# c-mote.net
KiCad netlist of a schematic drawn in Altium Designer
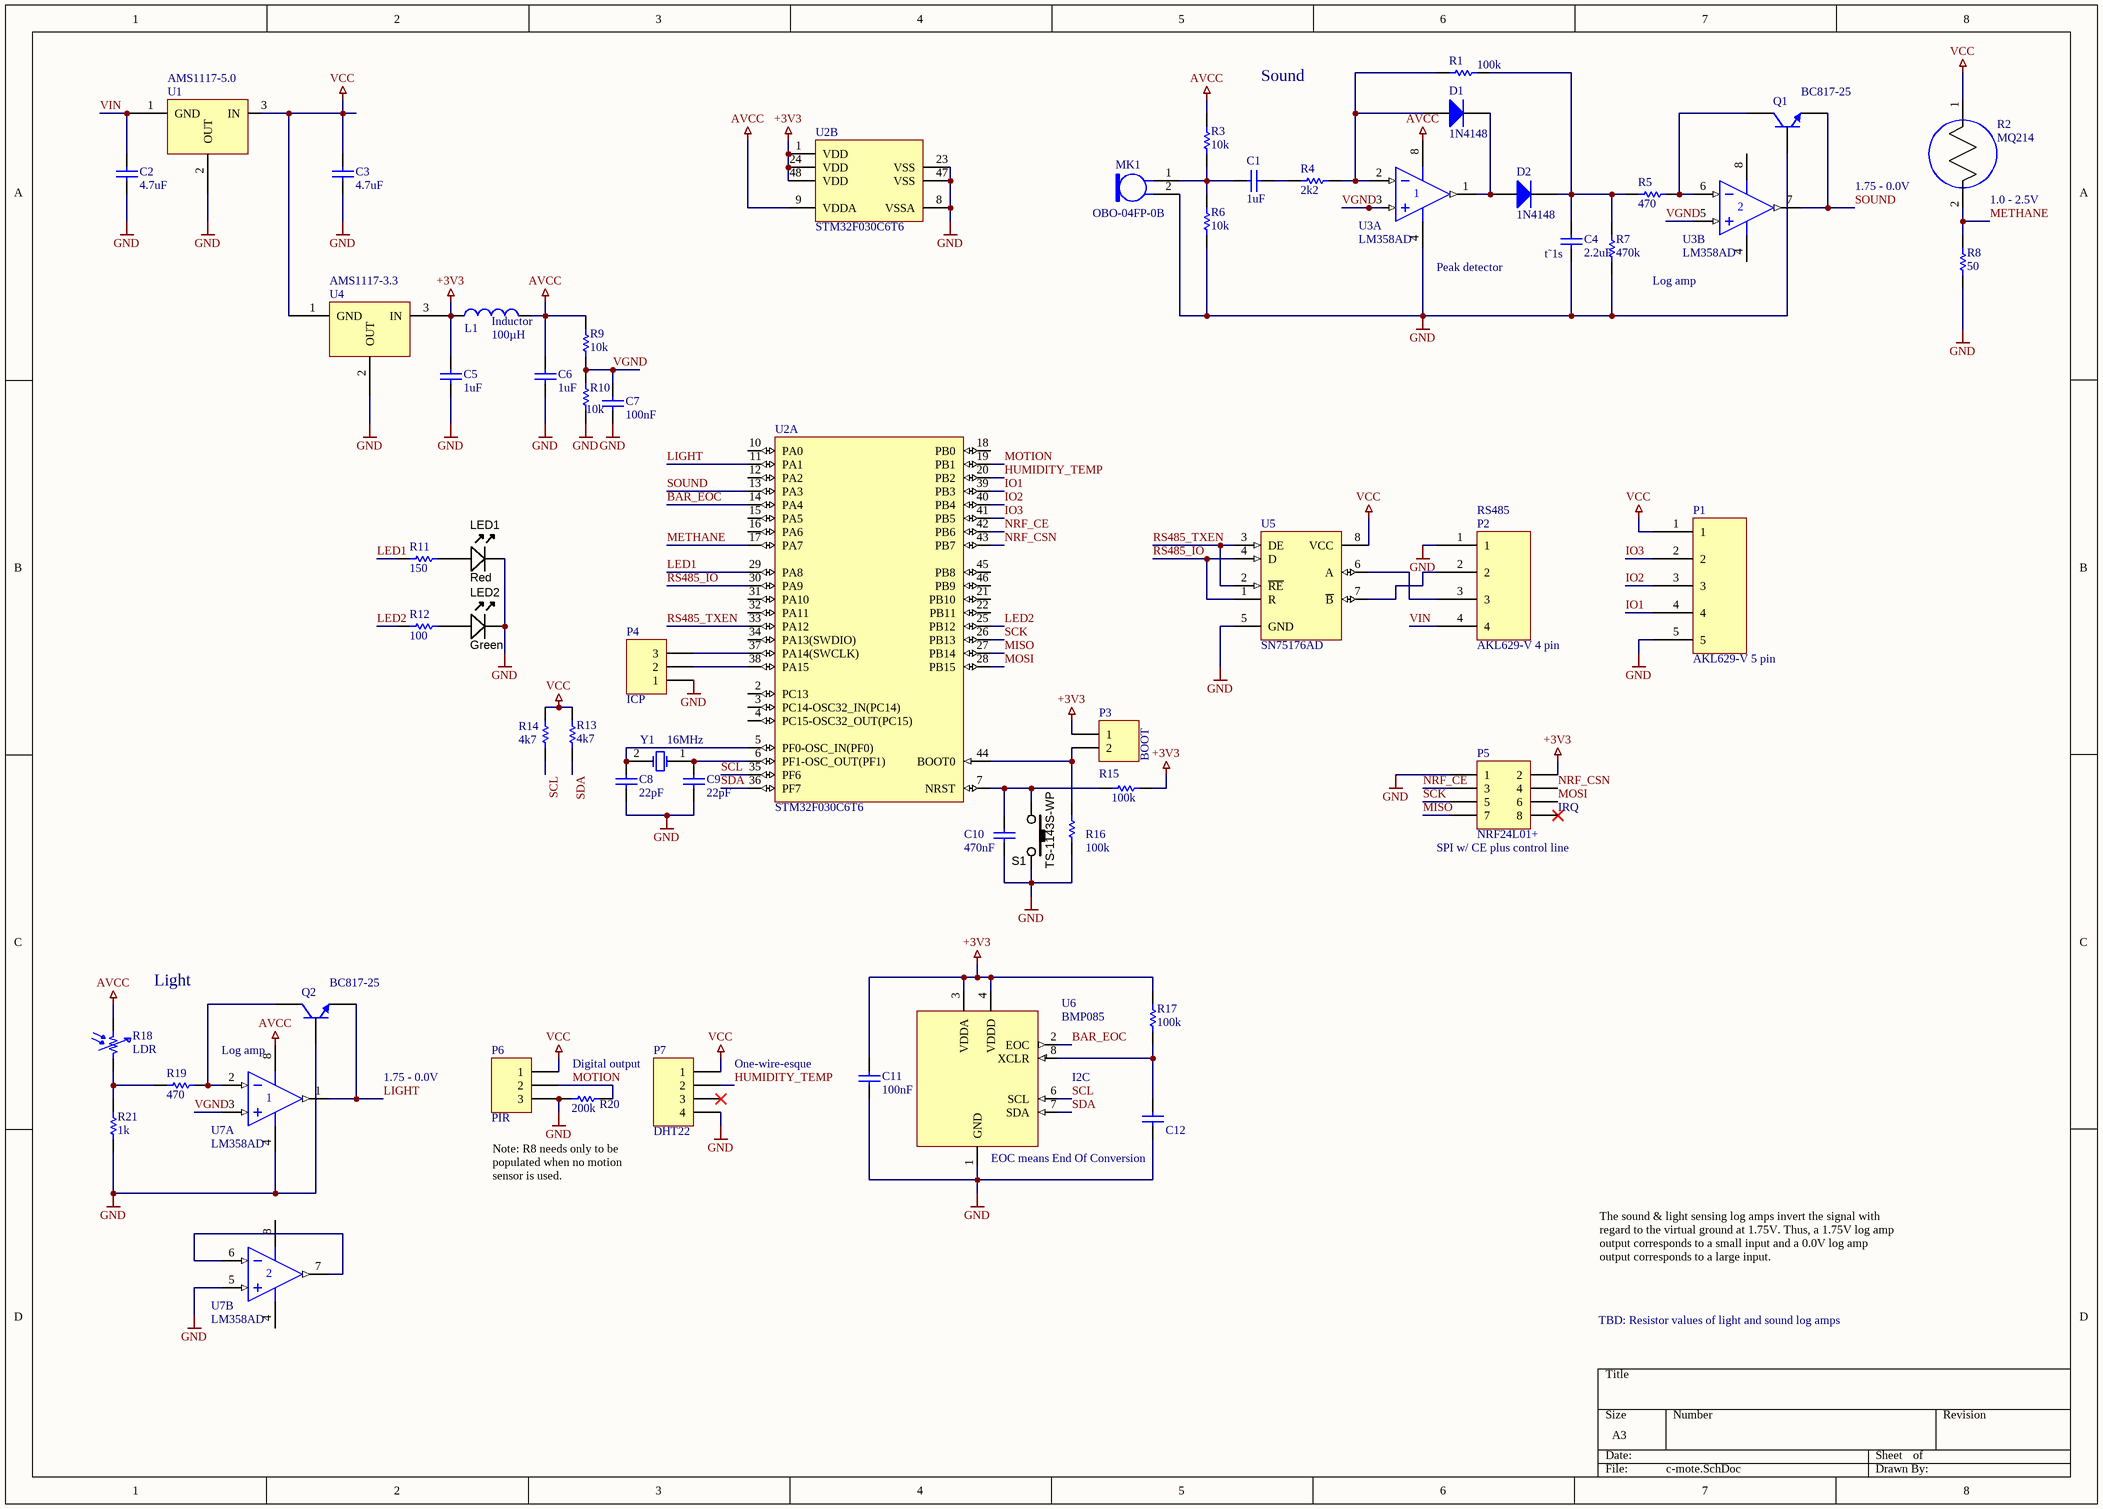
[diagram p0: c-mote.SchDoc]

(export (version "E")
  (design (tool "Eeschema 10.0.6"))
  (components
    (comp (ref "C1")
      (value "1uF")
      (footprint "CAPC0805(2012)145_M")
      (description "CAP 1uF 10V ±20% 0805 (2012 Metric) Thickness 1.45mm SMD")
      (fields (field (name "TOLERANCE") "±20%") (field (name "Comment") "CAP 1uF 10V 0805(2012)"))
      (libsource (lib "Altium Content Vault") (part "CMP-1036-04740-1"))
    )
    (comp (ref "C2")
      (value "4.7uF")
      (footprint "CAPC0805(2012)145_N")
      (description "CAP 4.7uF 10V ±20% 0805 (2012 Metric) Thickness 1.45mm SMD")
      (fields (field (name "TOLERANCE") "±20%") (field (name "Comment") "CAP 4.7uF 10V 0805(2012)"))
      (libsource (lib "Altium Content Vault") (part "CMP-1036-04884-1"))
    )
    (comp (ref "C3")
      (value "4.7uF")
      (footprint "CAPC0805(2012)145_N")
      (description "CAP 4.7uF 10V ±20% 0805 (2012 Metric) Thickness 1.45mm SMD")
      (fields (field (name "TOLERANCE") "±20%") (field (name "Comment") "CAP 4.7uF 10V 0805(2012)"))
      (libsource (lib "Altium Content Vault") (part "CMP-1036-04884-1"))
    )
    (comp (ref "C4")
      (value "2.2uF")
      (footprint "CAPC0805(2012)145_N")
      (description "CAP 2.2uF 10V ±10% 0805 (2012 Metric) Thickness 1.45mm SMD")
      (fields (field (name "TOLERANCE") "±10%") (field (name "Comment") "CAP 2.2uF 10V 0805(2012)"))
      (libsource (lib "Altium Content Vault") (part "CMP-1036-04824-1"))
    )
    (comp (ref "C5")
      (value "1uF")
      (footprint "CAPC0805(2012)145_M")
      (description "CAP 1uF 10V ±20% 0805 (2012 Metric) Thickness 1.45mm SMD")
      (fields (field (name "TOLERANCE") "±20%") (field (name "Comment") "CAP 1uF 10V 0805(2012)"))
      (libsource (lib "Altium Content Vault") (part "CMP-1036-04740-1"))
    )
    (comp (ref "C6")
      (value "1uF")
      (footprint "CAPC0805(2012)145_M")
      (description "CAP 1uF 10V ±20% 0805 (2012 Metric) Thickness 1.45mm SMD")
      (fields (field (name "TOLERANCE") "±20%") (field (name "Comment") "CAP 1uF 10V 0805(2012)"))
      (libsource (lib "Altium Content Vault") (part "CMP-1036-04740-1"))
    )
    (comp (ref "C7")
      (value "100nF")
      (footprint "CAPC0805(2012)100_M")
      (description "CAP 100nF 10V ±10% 0805 (2012 Metric) Thickness 1mm SMD")
      (fields (field (name "TOLERANCE") "±10%") (field (name "Comment") "CAP 100nF 10V 0805(2012)"))
      (libsource (lib "Altium Content Vault") (part "CMP-1036-04394-1"))
    )
    (comp (ref "C8")
      (value "22pF")
      (footprint "CAPC0805(2012)100_M")
      (description "CAP 22pF 10V ±5% 0805 (2012 Metric) Thickness 1mm SMD")
      (fields (field (name "TOLERANCE") "±5%") (field (name "Comment") "CAP 22pF 10V 0805(2012)"))
      (libsource (lib "Altium Content Vault") (part "CMP-1036-01210-1"))
    )
    (comp (ref "C9")
      (value "22pF")
      (footprint "CAPC0805(2012)100_M")
      (description "CAP 22pF 10V ±5% 0805 (2012 Metric) Thickness 1mm SMD")
      (fields (field (name "TOLERANCE") "±5%") (field (name "Comment") "CAP 22pF 10V 0805(2012)"))
      (libsource (lib "Altium Content Vault") (part "CMP-1036-01210-1"))
    )
    (comp (ref "C10")
      (value "470nF")
      (footprint "CAPC0805(2012)145_M")
      (description "CAP 470nF 10V ±10% 0805 (2012 Metric) Thickness 1.45mm SMD")
      (fields (field (name "TOLERANCE") "±10%") (field (name "Comment") "CAP 470nF 10V 0805(2012)"))
      (libsource (lib "Altium Content Vault") (part "CMP-1036-04631-1"))
    )
    (comp (ref "C11")
      (value "100nF")
      (footprint "CAPC0805(2012)100_M")
      (description "CAP 100nF 10V ±10% 0805 (2012 Metric) Thickness 1mm SMD")
      (fields (field (name "TOLERANCE") "±10%") (field (name "Comment") "CAP 100nF 10V 0805(2012)"))
      (libsource (lib "Altium Content Vault") (part "CMP-1036-04394-1"))
    )
    (comp (ref "C12")
      (value "CAP 10nF 10V 0805(2012)")
      (footprint "CAPC0805(2012)100_L")
      (description "CAP 10nF 10V ±10% 0805 (2012 Metric) Thickness 1mm SMD")
      (fields (field (name "TOLERANCE") "±10%"))
      (libsource (lib "Altium Content Vault") (part "CAP"))
    )
    (comp (ref "D1")
      (value "1N4148")
      (footprint "SOD-323F")
      (description "High Conductance Fast Diode")
      (fields (field (name "PUBLISHER") "Altium Limited"))
      (libsource (lib "FSC Discrete Diode") (part "1N4148"))
    )
    (comp (ref "D2")
      (value "1N4148")
      (footprint "SOD-323F")
      (description "High Conductance Fast Diode")
      (fields (field (name "PUBLISHER") "Altium Limited"))
      (libsource (lib "FSC Discrete Diode") (part "1N4148"))
    )
    (comp (ref "L1")
      (value "Inductor")
      (footprint "INDC3216")
      (fields (field (name "ALTIUM_VALUE") "100µH") (field (name "PUBLISHER") "Altium Limited"))
      (libsource (lib "Miscellaneous Devices") (part "Inductor"))
    )
    (comp (ref "LED1")
      (value "~")
      (footprint "LED-0805-K")
      (description "LED 0805 SMD Red 6mcd 621nm")
      (fields (field (name "COLOR") "Red"))
      (libsource (lib "PBL - Light Sources") (part "LED_SMD_Red_0805_6mcd"))
    )
    (comp (ref "LED2")
      (value "~")
      (footprint "LED-0805-K")
      (description "LED, 0805 SMD, Green")
      (fields (field (name "COLOR") "Green"))
      (libsource (lib "PBL - Light Sources") (part "LED_SMD_Green_0805_6mcd"))
    )
    (comp (ref "MK1")
      (value "OBO-04FP-0B")
      (footprint "OBO-04FP-0B")
      (description "Microphone")
      (fields (field (name "PUBLISHER") "Altium Limited"))
      (libsource (lib "Miscellaneous Devices") (part "Mic2"))
    )
    (comp (ref "P1") (value "AKL629-V 5 pin") (libsource (lib "auxcomp") (part "AKL629-V 5 pin")))
    (comp (ref "P2") (value "AKL629-V 4 pin") (libsource (lib "auxcomp") (part "AKL629-V 4 pin")))
    (comp (ref "P3")
      (value "BOOT")
      (footprint "HDR1X2")
      (description "Header, 2-Pin")
      (fields (field (name "PUBLISHER") "Altium Limited"))
      (libsource (lib "Miscellaneous Connectors") (part "Header 2"))
    )
    (comp (ref "P4")
      (value "ICP")
      (footprint "HDR1X3")
      (description "Header, 3-Pin")
      (fields (field (name "PUBLISHER") "Altium Limited"))
      (libsource (lib "") (part "Header 3_1"))
    )
    (comp (ref "P5")
      (value "NRF24L01+")
      (footprint "HDR2X4")
      (description "Header, 4-Pin, Dual row")
      (fields (field (name "PUBLISHER") "Altium Limited"))
      (libsource (lib "Miscellaneous Connectors") (part "Header 4X2"))
    )
    (comp (ref "P6")
      (value "PIR")
      (footprint "China-PIR sensor")
      (description "Header, 3-Pin")
      (fields (field (name "PUBLISHER") "Altium Limited"))
      (libsource (lib "Miscellaneous Connectors") (part "Header 3"))
    )
    (comp (ref "P7")
      (value "DHT22")
      (footprint "DHT22-H")
      (description "Header, 4-Pin")
      (fields (field (name "PUBLISHER") "Altium Limited"))
      (libsource (lib "Miscellaneous Connectors") (part "Header 4"))
    )
    (comp (ref "Q1")
      (value "BC817-25")
      (footprint "SOT23_N")
      (description "NPN General Purpose Amplifier")
      (fields (field (name "PUBLISHER") "Altium Limited"))
      (libsource (lib "FSC Discrete BJT") (part "BC817-25"))
    )
    (comp (ref "Q2")
      (value "BC817-25")
      (footprint "SOT23_N")
      (description "NPN General Purpose Amplifier")
      (fields (field (name "PUBLISHER") "Altium Limited"))
      (libsource (lib "FSC Discrete BJT") (part "BC817-25"))
    )
    (comp (ref "R1")
      (value "100k")
      (footprint "6-0805")
      (fields (field (name "PUBLISHER") "Altium Limited"))
      (libsource (lib "Panasonic Resistor") (part "ERJ6RB"))
    )
    (comp (ref "R2") (value "MQ214") (footprint "MQ214") (libsource (lib "auxcomp") (part "MQ214")))
    (comp (ref "R3")
      (value "10k")
      (footprint "6-0805")
      (fields (field (name "PUBLISHER") "Altium Limited"))
      (libsource (lib "Panasonic Resistor") (part "ERJ6RB"))
    )
    (comp (ref "R4")
      (value "2k2")
      (footprint "6-0805")
      (fields (field (name "PUBLISHER") "Altium Limited"))
      (libsource (lib "Panasonic Resistor") (part "ERJ6RB"))
    )
    (comp (ref "R5")
      (value "470")
      (footprint "6-0805")
      (fields (field (name "PUBLISHER") "Altium Limited"))
      (libsource (lib "Panasonic Resistor") (part "ERJ6RB"))
    )
    (comp (ref "R6")
      (value "10k")
      (footprint "6-0805")
      (fields (field (name "PUBLISHER") "Altium Limited"))
      (libsource (lib "Panasonic Resistor") (part "ERJ6RB"))
    )
    (comp (ref "R7")
      (value "470k")
      (footprint "6-0805")
      (fields (field (name "PUBLISHER") "Altium Limited"))
      (libsource (lib "Panasonic Resistor") (part "ERJ6RB"))
    )
    (comp (ref "R8")
      (value "50")
      (footprint "6-0805")
      (fields (field (name "PUBLISHER") "Altium Limited"))
      (libsource (lib "Panasonic Resistor") (part "ERJ6RB"))
    )
    (comp (ref "R9")
      (value "10k")
      (footprint "6-0805")
      (fields (field (name "PUBLISHER") "Altium Limited"))
      (libsource (lib "Panasonic Resistor") (part "ERJ6RB"))
    )
    (comp (ref "R10")
      (value "10k")
      (footprint "6-0805")
      (fields (field (name "PUBLISHER") "Altium Limited"))
      (libsource (lib "Panasonic Resistor") (part "ERJ6RB"))
    )
    (comp (ref "R11")
      (value "150")
      (footprint "6-0805")
      (fields (field (name "PUBLISHER") "Altium Limited"))
      (libsource (lib "Panasonic Resistor") (part "ERJ6RB"))
    )
    (comp (ref "R12")
      (value "100")
      (footprint "6-0805")
      (fields (field (name "PUBLISHER") "Altium Limited"))
      (libsource (lib "Panasonic Resistor") (part "ERJ6RB"))
    )
    (comp (ref "R13")
      (value "4k7")
      (footprint "6-0805")
      (fields (field (name "PUBLISHER") "Altium Limited"))
      (libsource (lib "Panasonic Resistor") (part "ERJ6RB"))
    )
    (comp (ref "R14")
      (value "4k7")
      (footprint "6-0805")
      (fields (field (name "PUBLISHER") "Altium Limited"))
      (libsource (lib "Panasonic Resistor") (part "ERJ6RB"))
    )
    (comp (ref "R15")
      (value "100k")
      (footprint "6-0805")
      (fields (field (name "PUBLISHER") "Altium Limited"))
      (libsource (lib "Panasonic Resistor") (part "ERJ6RB"))
    )
    (comp (ref "R16")
      (value "100k")
      (footprint "6-0805")
      (fields (field (name "PUBLISHER") "Altium Limited"))
      (libsource (lib "Panasonic Resistor") (part "ERJ6RB"))
    )
    (comp (ref "R17")
      (value "100k")
      (footprint "6-0805")
      (fields (field (name "PUBLISHER") "Altium Limited"))
      (libsource (lib "Panasonic Resistor") (part "ERJ6RB"))
    )
    (comp (ref "R18")
      (value "LDR")
      (footprint "KE-10720")
      (description "KE-10720")
      (libsource (lib "auxcomp") (part "LDR"))
    )
    (comp (ref "R19")
      (value "470")
      (footprint "6-0805")
      (fields (field (name "PUBLISHER") "Altium Limited"))
      (libsource (lib "Panasonic Resistor") (part "ERJ6RB"))
    )
    (comp (ref "R20")
      (value "200k")
      (footprint "6-0805")
      (fields (field (name "PUBLISHER") "Altium Limited"))
      (libsource (lib "Panasonic Resistor") (part "ERJ6RB"))
    )
    (comp (ref "R21")
      (value "1k")
      (footprint "6-0805")
      (fields (field (name "PUBLISHER") "Altium Limited"))
      (libsource (lib "Panasonic Resistor") (part "ERJ6RB"))
    )
    (comp (ref "S1")
      (value "TS-1143S-WP")
      (footprint "TS-1143S")
      (description "Switch SMD Tact 4.3mm Stem")
      (libsource (lib "PBL - Switches") (part "SW_SMD_PB_4.3mm"))
    )
    (comp (ref "U1") (value "AMS1117-5.0") (footprint "SOT223") (libsource (lib "auxcomp") (part "AMS1117")))
    (comp (ref "U2")
      (value "STM32F030C6T6")
      (footprint "STM-LQFP48_N")
      (libsource (lib "Altium Content Vault") (part "MC-ARM-STM32F030-SQ48"))
    )
    (comp (ref "U3")
      (value "LM358AD")
      (footprint "SOIC127P600X175-8AN")
      (description "Dual Operational Amplifier")
      (fields (field (name "PUBLISHER") "Altium Limited"))
      (libsource (lib "TI Operational Amplifier") (part "LM358AD"))
    )
    (comp (ref "U4") (value "AMS1117-3.3") (footprint "SOT223") (libsource (lib "auxcomp") (part "AMS1117")))
    (comp (ref "U5")
      (value "SN75176AD")
      (footprint "SOIC127P600X175-8AN")
      (description "Differential Bus Transceiver")
      (fields (field (name "PUBLISHER") "Altium Limited"))
      (libsource (lib "TI Interface Line Transceiver") (part "SN75176AD"))
    )
    (comp (ref "U6") (value "BMP085") (footprint "BMP085") (libsource (lib "auxcomp") (part "BMP085")))
    (comp (ref "U7")
      (value "LM358AD")
      (footprint "SOIC127P600X175-8AN")
      (description "Dual Operational Amplifier")
      (fields (field (name "PUBLISHER") "Altium Limited"))
      (libsource (lib "TI Operational Amplifier") (part "LM358AD"))
    )
    (comp (ref "Y1")
      (value "16MHz")
      (footprint "HC49/US")
      (description "Crystal")
      (fields (field (name "PUBLISHER") "Altium Limited"))
      (libsource (lib "Miscellaneous Devices") (part "XTAL"))
    )
  )
  (nets
    (net (code "1") (name "+3V3") (class "Default")
      (node (ref "C11") (pin "2") (pinfunction "2_2") (pintype "passive"))
      (node (ref "C5") (pin "2") (pinfunction "2_2") (pintype "passive"))
      (node (ref "L1") (pin "1") (pinfunction "1_1") (pintype "passive"))
      (node (ref "P3") (pin "1") (pinfunction "1_1") (pintype "passive"))
      (node (ref "P5") (pin "2") (pinfunction "2_2") (pintype "passive"))
      (node (ref "R15") (pin "2") (pinfunction "2_2") (pintype "passive"))
      (node (ref "R17") (pin "2") (pinfunction "2_2") (pintype "passive"))
      (node (ref "U2") (pin "1") (pinfunction "VDD_1") (pintype "power_in"))
      (node (ref "U2") (pin "24") (pinfunction "VDD_24") (pintype "power_in"))
      (node (ref "U2") (pin "48") (pinfunction "VDD_48") (pintype "power_in"))
      (node (ref "U4") (pin "3") (pinfunction "IN_3") (pintype "passive"))
      (node (ref "U6") (pin "3") (pinfunction "VDDA_3") (pintype "power_in"))
      (node (ref "U6") (pin "4") (pinfunction "VDDD_4") (pintype "power_in"))
    )
    (net (code "2") (name "/BAR_EOC") (class "Default")
      (node (ref "U2") (pin "14") (pinfunction "PA4_14") (pintype "bidirectional"))
      (node (ref "U6") (pin "2") (pinfunction "EOC_2") (pintype "output"))
    )
    (net (code "3") (name "/HUMIDITY_TEMP") (class "Default")
      (node (ref "P7") (pin "2") (pinfunction "2_2") (pintype "passive"))
      (node (ref "U2") (pin "20") (pinfunction "PB2_20") (pintype "bidirectional"))
    )
    (net (code "4") (name "/IO1") (class "Default")
      (node (ref "P1") (pin "4") (pinfunction "4_4") (pintype "passive"))
      (node (ref "U2") (pin "39") (pinfunction "PB3_39") (pintype "bidirectional"))
    )
    (net (code "5") (name "/IO2") (class "Default")
      (node (ref "P1") (pin "3") (pinfunction "3_3") (pintype "passive"))
      (node (ref "U2") (pin "40") (pinfunction "PB4_40") (pintype "bidirectional"))
    )
    (net (code "6") (name "/IO3") (class "Default")
      (node (ref "P1") (pin "2") (pinfunction "2_2") (pintype "passive"))
      (node (ref "U2") (pin "41") (pinfunction "PB5_41") (pintype "bidirectional"))
    )
    (net (code "7") (name "/LED1") (class "Default")
      (node (ref "R11") (pin "2") (pinfunction "2_2") (pintype "passive"))
      (node (ref "U2") (pin "29") (pinfunction "PA8_29") (pintype "bidirectional"))
    )
    (net (code "8") (name "/LED2") (class "Default")
      (node (ref "R12") (pin "2") (pinfunction "2_2") (pintype "passive"))
      (node (ref "U2") (pin "25") (pinfunction "PB12_25") (pintype "bidirectional"))
    )
    (net (code "9") (name "/LIGHT") (class "Default")
      (node (ref "Q2") (pin "2") (pinfunction "E_2") (pintype "passive"))
      (node (ref "U2") (pin "11") (pinfunction "PA1_11") (pintype "bidirectional"))
      (node (ref "U7") (pin "1") (pinfunction "OUT_1") (pintype "output"))
    )
    (net (code "10") (name "/METHANE") (class "Default")
      (node (ref "R2") (pin "2") (pintype "passive"))
      (node (ref "R8") (pin "2") (pinfunction "2_2") (pintype "passive"))
      (node (ref "U2") (pin "17") (pinfunction "PA7_17") (pintype "bidirectional"))
    )
    (net (code "11") (name "/MISO") (class "Default")
      (node (ref "P5") (pin "7") (pinfunction "7_7") (pintype "passive"))
      (node (ref "U2") (pin "27") (pinfunction "PB14_27") (pintype "bidirectional"))
    )
    (net (code "12") (name "/MOSI") (class "Default")
      (node (ref "P5") (pin "6") (pinfunction "6_6") (pintype "passive"))
      (node (ref "U2") (pin "28") (pinfunction "PB15_28") (pintype "bidirectional"))
    )
    (net (code "13") (name "/MOTION") (class "Default")
      (node (ref "P6") (pin "2") (pinfunction "2_2") (pintype "passive"))
      (node (ref "R20") (pin "2") (pinfunction "2_2") (pintype "passive"))
      (node (ref "U2") (pin "19") (pinfunction "PB1_19") (pintype "bidirectional"))
    )
    (net (code "14") (name "/NRF_CE") (class "Default")
      (node (ref "P5") (pin "3") (pinfunction "3_3") (pintype "passive"))
      (node (ref "U2") (pin "42") (pinfunction "PB6_42") (pintype "bidirectional"))
    )
    (net (code "15") (name "/NRF_CSN") (class "Default")
      (node (ref "P5") (pin "4") (pinfunction "4_4") (pintype "passive"))
      (node (ref "U2") (pin "43") (pinfunction "PB7_43") (pintype "bidirectional"))
    )
    (net (code "16") (name "/RS485_IO") (class "Default")
      (node (ref "U2") (pin "30") (pinfunction "PA9_30") (pintype "bidirectional"))
      (node (ref "U5") (pin "1") (pinfunction "R_1") (pintype "tri_state"))
      (node (ref "U5") (pin "4") (pinfunction "D_4") (pintype "input"))
    )
    (net (code "17") (name "/RS485_TXEN") (class "Default")
      (node (ref "U2") (pin "33") (pinfunction "PA12_33") (pintype "bidirectional"))
      (node (ref "U5") (pin "2") (pinfunction "~{RE}_2") (pintype "input"))
      (node (ref "U5") (pin "3") (pinfunction "DE_3") (pintype "input"))
    )
    (net (code "18") (name "/SCK") (class "Default")
      (node (ref "P5") (pin "5") (pinfunction "5_5") (pintype "passive"))
      (node (ref "U2") (pin "26") (pinfunction "PB13_26") (pintype "bidirectional"))
    )
    (net (code "19") (name "/SCL") (class "Default")
      (node (ref "R14") (pin "2") (pinfunction "2_2") (pintype "passive"))
      (node (ref "U2") (pin "35") (pinfunction "PF6_35") (pintype "bidirectional"))
      (node (ref "U6") (pin "6") (pinfunction "SCL_6") (pintype "input"))
    )
    (net (code "20") (name "/SDA") (class "Default")
      (node (ref "R13") (pin "2") (pinfunction "2_2") (pintype "passive"))
      (node (ref "U2") (pin "36") (pinfunction "PF7_36") (pintype "bidirectional"))
      (node (ref "U6") (pin "7") (pinfunction "SDA_7") (pintype "input"))
    )
    (net (code "21") (name "/SOUND") (class "Default")
      (node (ref "Q1") (pin "2") (pinfunction "E_2") (pintype "passive"))
      (node (ref "U2") (pin "13") (pinfunction "PA3_13") (pintype "bidirectional"))
      (node (ref "U3") (pin "7") (pinfunction "OUT_7") (pintype "output"))
    )
    (net (code "22") (name "/VGND") (class "Default")
      (node (ref "C7") (pin "2") (pinfunction "2_2") (pintype "passive"))
      (node (ref "R10") (pin "2") (pinfunction "2_2") (pintype "passive"))
      (node (ref "R9") (pin "1") (pinfunction "1_1") (pintype "passive"))
      (node (ref "U3") (pin "3") (pinfunction "IN+_3") (pintype "input"))
      (node (ref "U3") (pin "5") (pinfunction "IN+_5") (pintype "input"))
      (node (ref "U7") (pin "3") (pinfunction "IN+_3") (pintype "input"))
    )
    (net (code "23") (name "/VIN") (class "Default")
      (node (ref "C2") (pin "2") (pinfunction "2_2") (pintype "passive"))
      (node (ref "P2") (pin "4") (pinfunction "4_4") (pintype "passive"))
      (node (ref "U1") (pin "1") (pinfunction "GND_1") (pintype "passive"))
    )
    (net (code "24") (name "AVCC") (class "Default")
      (node (ref "C6") (pin "2") (pinfunction "2_2") (pintype "passive"))
      (node (ref "L1") (pin "2") (pinfunction "2_2") (pintype "passive"))
      (node (ref "R18") (pin "1") (pinfunction "1_1") (pintype "passive"))
      (node (ref "R3") (pin "2") (pinfunction "2_2") (pintype "passive"))
      (node (ref "R9") (pin "2") (pinfunction "2_2") (pintype "passive"))
      (node (ref "U2") (pin "9") (pinfunction "VDDA_9") (pintype "power_in"))
      (node (ref "U3") (pin "8") (pinfunction "V+_8") (pintype "power_in"))
      (node (ref "U7") (pin "8") (pinfunction "V+_8") (pintype "power_in"))
    )
    (net (code "25") (name "GND") (class "Default")
      (node (ref "C10") (pin "1") (pinfunction "1_1") (pintype "passive"))
      (node (ref "C11") (pin "1") (pinfunction "1_1") (pintype "passive"))
      (node (ref "C12") (pin "1") (pinfunction "1_1") (pintype "passive"))
      (node (ref "C2") (pin "1") (pinfunction "1_1") (pintype "passive"))
      (node (ref "C3") (pin "1") (pinfunction "1_1") (pintype "passive"))
      (node (ref "C4") (pin "1") (pinfunction "1_1") (pintype "passive"))
      (node (ref "C5") (pin "1") (pinfunction "1_1") (pintype "passive"))
      (node (ref "C6") (pin "1") (pinfunction "1_1") (pintype "passive"))
      (node (ref "C7") (pin "1") (pinfunction "1_1") (pintype "passive"))
      (node (ref "C8") (pin "1") (pinfunction "1_1") (pintype "passive"))
      (node (ref "C9") (pin "1") (pinfunction "1_1") (pintype "passive"))
      (node (ref "LED1") (pin "K") (pinfunction "K_K") (pintype "passive"))
      (node (ref "LED2") (pin "K") (pinfunction "K_K") (pintype "passive"))
      (node (ref "MK1") (pin "2") (pinfunction "2_2") (pintype "passive"))
      (node (ref "P1") (pin "5") (pinfunction "5_5") (pintype "passive"))
      (node (ref "P2") (pin "1") (pinfunction "1_1") (pintype "passive"))
      (node (ref "P4") (pin "1") (pinfunction "1_1") (pintype "passive"))
      (node (ref "P5") (pin "1") (pinfunction "1_1") (pintype "passive"))
      (node (ref "P6") (pin "3") (pinfunction "3_3") (pintype "passive"))
      (node (ref "P7") (pin "4") (pinfunction "4_4") (pintype "passive"))
      (node (ref "Q1") (pin "1") (pinfunction "B_1") (pintype "passive"))
      (node (ref "Q2") (pin "1") (pinfunction "B_1") (pintype "passive"))
      (node (ref "R10") (pin "1") (pinfunction "1_1") (pintype "passive"))
      (node (ref "R16") (pin "1") (pinfunction "1_1") (pintype "passive"))
      (node (ref "R20") (pin "1") (pinfunction "1_1") (pintype "passive"))
      (node (ref "R21") (pin "2") (pinfunction "2_2") (pintype "passive"))
      (node (ref "R6") (pin "1") (pinfunction "1_1") (pintype "passive"))
      (node (ref "R7") (pin "2") (pinfunction "2_2") (pintype "passive"))
      (node (ref "R8") (pin "1") (pinfunction "1_1") (pintype "passive"))
      (node (ref "S1") (pin "2") (pintype "passive"))
      (node (ref "U1") (pin "2") (pinfunction "OUT_2") (pintype "passive"))
      (node (ref "U2") (pin "23") (pinfunction "VSS_23") (pintype "power_in"))
      (node (ref "U2") (pin "47") (pinfunction "VSS_47") (pintype "power_in"))
      (node (ref "U2") (pin "8") (pinfunction "VSSA_8") (pintype "power_in"))
      (node (ref "U3") (pin "4") (pinfunction "V-_4") (pintype "power_in"))
      (node (ref "U4") (pin "2") (pinfunction "OUT_2") (pintype "passive"))
      (node (ref "U5") (pin "5") (pinfunction "GND_5") (pintype "power_in"))
      (node (ref "U6") (pin "1") (pinfunction "GND_1") (pintype "power_in"))
      (node (ref "U7") (pin "4") (pinfunction "V-_4") (pintype "power_in"))
      (node (ref "U7") (pin "5") (pinfunction "IN+_5") (pintype "input"))
    )
    (net (code "26") (name "Net-(C1-Pad1)") (class "Default")
      (node (ref "C1") (pin "1") (pinfunction "1_1") (pintype "passive"))
      (node (ref "R4") (pin "2") (pinfunction "2_2") (pintype "passive"))
    )
    (net (code "27") (name "Net-(C1-Pad2)") (class "Default")
      (node (ref "C1") (pin "2") (pinfunction "2_2") (pintype "passive"))
      (node (ref "MK1") (pin "1") (pinfunction "1_1") (pintype "passive"))
      (node (ref "R3") (pin "1") (pinfunction "1_1") (pintype "passive"))
      (node (ref "R6") (pin "2") (pinfunction "2_2") (pintype "passive"))
    )
    (net (code "28") (name "Net-(D1-A)") (class "Default")
      (node (ref "D1") (pin "1") (pinfunction "A_1") (pintype "passive"))
      (node (ref "R1") (pin "2") (pinfunction "2_2") (pintype "passive"))
      (node (ref "R4") (pin "1") (pinfunction "1_1") (pintype "passive"))
      (node (ref "U3") (pin "2") (pinfunction "IN-_2") (pintype "input"))
    )
    (net (code "29") (name "Net-(D1-K)") (class "Default")
      (node (ref "D1") (pin "2") (pinfunction "K_2") (pintype "passive"))
      (node (ref "D2") (pin "1") (pinfunction "A_1") (pintype "passive"))
      (node (ref "U3") (pin "1") (pinfunction "OUT_1") (pintype "output"))
    )
    (net (code "30") (name "Net-(D2-K)") (class "Default")
      (node (ref "C4") (pin "2") (pinfunction "2_2") (pintype "passive"))
      (node (ref "D2") (pin "2") (pinfunction "K_2") (pintype "passive"))
      (node (ref "R1") (pin "1") (pinfunction "1_1") (pintype "passive"))
      (node (ref "R5") (pin "1") (pinfunction "1_1") (pintype "passive"))
      (node (ref "R7") (pin "1") (pinfunction "1_1") (pintype "passive"))
    )
    (net (code "31") (name "Net-(LED1-PadA)") (class "Default")
      (node (ref "LED1") (pin "A") (pinfunction "A_A") (pintype "passive"))
      (node (ref "R11") (pin "1") (pinfunction "1_1") (pintype "passive"))
    )
    (net (code "32") (name "Net-(LED2-PadA)") (class "Default")
      (node (ref "LED2") (pin "A") (pinfunction "A_A") (pintype "passive"))
      (node (ref "R12") (pin "1") (pinfunction "1_1") (pintype "passive"))
    )
    (net (code "33") (name "Net-(Q1-C)") (class "Default")
      (node (ref "Q1") (pin "3") (pinfunction "C_3") (pintype "passive"))
      (node (ref "R5") (pin "2") (pinfunction "2_2") (pintype "passive"))
      (node (ref "U3") (pin "6") (pinfunction "IN-_6") (pintype "input"))
    )
    (net (code "34") (name "Net-(Q2-C)") (class "Default")
      (node (ref "Q2") (pin "3") (pinfunction "C_3") (pintype "passive"))
      (node (ref "R19") (pin "2") (pinfunction "2_2") (pintype "passive"))
      (node (ref "U7") (pin "2") (pinfunction "IN-_2") (pintype "input"))
    )
    (net (code "35") (name "Net-(R18-Pad2)") (class "Default")
      (node (ref "R18") (pin "2") (pinfunction "2_2") (pintype "passive"))
      (node (ref "R19") (pin "1") (pinfunction "1_1") (pintype "passive"))
      (node (ref "R21") (pin "1") (pinfunction "1_1") (pintype "passive"))
    )
    (net (code "36") (name "Net-(U2A-BOOT0)") (class "Default")
      (node (ref "P3") (pin "2") (pinfunction "2_2") (pintype "passive"))
      (node (ref "R16") (pin "2") (pinfunction "2_2") (pintype "passive"))
      (node (ref "U2") (pin "44") (pinfunction "BOOT0_44") (pintype "input"))
    )
    (net (code "37") (name "Net-(U2A-NRST)") (class "Default")
      (node (ref "C10") (pin "2") (pinfunction "2_2") (pintype "passive"))
      (node (ref "R15") (pin "1") (pinfunction "1_1") (pintype "passive"))
      (node (ref "S1") (pin "1") (pintype "passive"))
      (node (ref "U2") (pin "7") (pinfunction "NRST_7") (pintype "bidirectional"))
    )
    (net (code "38") (name "Net-(U2A-PA14(SWCLK))") (class "Default")
      (node (ref "P4") (pin "3") (pinfunction "3_3") (pintype "passive"))
      (node (ref "U2") (pin "37") (pinfunction "PA14(SWCLK)_37") (pintype "bidirectional"))
    )
    (net (code "39") (name "Net-(U2A-PA15)") (class "Default")
      (node (ref "P4") (pin "2") (pinfunction "2_2") (pintype "passive"))
      (node (ref "U2") (pin "38") (pinfunction "PA15_38") (pintype "bidirectional"))
    )
    (net (code "40") (name "Net-(U2A-PF0-OSC_IN(PF0))") (class "Default")
      (node (ref "C8") (pin "2") (pinfunction "2_2") (pintype "passive"))
      (node (ref "U2") (pin "5") (pinfunction "PF0-OSC_IN(PF0)_5") (pintype "bidirectional"))
      (node (ref "Y1") (pin "2") (pinfunction "OSC2_2") (pintype "passive"))
    )
    (net (code "41") (name "Net-(U2A-PF1-OSC_OUT(PF1))") (class "Default")
      (node (ref "C9") (pin "2") (pinfunction "2_2") (pintype "passive"))
      (node (ref "U2") (pin "6") (pinfunction "PF1-OSC_OUT(PF1)_6") (pintype "bidirectional"))
      (node (ref "Y1") (pin "1") (pinfunction "OSC1_1") (pintype "passive"))
    )
    (net (code "42") (name "Net-(U5-A)") (class "Default")
      (node (ref "P2") (pin "3") (pinfunction "3_3") (pintype "passive"))
      (node (ref "U5") (pin "6") (pinfunction "A_6") (pintype "bidirectional"))
    )
    (net (code "43") (name "Net-(U5-~{B})") (class "Default")
      (node (ref "P2") (pin "2") (pinfunction "2_2") (pintype "passive"))
      (node (ref "U5") (pin "7") (pinfunction "~{B}_7") (pintype "bidirectional"))
    )
    (net (code "44") (name "Net-(U6-XCLR)") (class "Default")
      (node (ref "C12") (pin "2") (pinfunction "2_2") (pintype "passive"))
      (node (ref "R17") (pin "1") (pinfunction "1_1") (pintype "passive"))
      (node (ref "U6") (pin "8") (pinfunction "XCLR_8") (pintype "input"))
    )
    (net (code "45") (name "Net-(U7B-IN-)") (class "Default")
      (node (ref "U7") (pin "6") (pinfunction "IN-_6") (pintype "input"))
      (node (ref "U7") (pin "7") (pinfunction "OUT_7") (pintype "output"))
    )
    (net (code "46") (name "VCC") (class "Default")
      (node (ref "C3") (pin "2") (pinfunction "2_2") (pintype "passive"))
      (node (ref "P1") (pin "1") (pinfunction "1_1") (pintype "passive"))
      (node (ref "P6") (pin "1") (pinfunction "1_1") (pintype "passive"))
      (node (ref "P7") (pin "1") (pinfunction "1_1") (pintype "passive"))
      (node (ref "R13") (pin "1") (pinfunction "1_1") (pintype "passive"))
      (node (ref "R14") (pin "1") (pinfunction "1_1") (pintype "passive"))
      (node (ref "R2") (pin "1") (pintype "passive"))
      (node (ref "U1") (pin "3") (pinfunction "IN_3") (pintype "passive"))
      (node (ref "U4") (pin "1") (pinfunction "GND_1") (pintype "passive"))
      (node (ref "U5") (pin "8") (pinfunction "VCC_8") (pintype "power_in"))
    )
    (net (code "47") (name "unconnected-(P5-Pad8)") (class "Default")
      (node (ref "P5") (pin "8") (pinfunction "8_8") (pintype "passive+no_connect"))
    )
    (net (code "48") (name "unconnected-(P7-Pad3)") (class "Default")
      (node (ref "P7") (pin "3") (pinfunction "3_3") (pintype "passive+no_connect"))
    )
    (net (code "49") (name "unconnected-(U2A-PA0-Pad10)") (class "Default")
      (node (ref "U2") (pin "10") (pinfunction "PA0_10") (pintype "bidirectional"))
    )
    (net (code "50") (name "unconnected-(U2A-PA2-Pad12)") (class "Default")
      (node (ref "U2") (pin "12") (pinfunction "PA2_12") (pintype "bidirectional"))
    )
    (net (code "51") (name "unconnected-(U2A-PA5-Pad15)") (class "Default")
      (node (ref "U2") (pin "15") (pinfunction "PA5_15") (pintype "bidirectional"))
    )
    (net (code "52") (name "unconnected-(U2A-PA6-Pad16)") (class "Default")
      (node (ref "U2") (pin "16") (pinfunction "PA6_16") (pintype "bidirectional"))
    )
    (net (code "53") (name "unconnected-(U2A-PA10-Pad31)") (class "Default")
      (node (ref "U2") (pin "31") (pinfunction "PA10_31") (pintype "bidirectional"))
    )
    (net (code "54") (name "unconnected-(U2A-PA11-Pad32)") (class "Default")
      (node (ref "U2") (pin "32") (pinfunction "PA11_32") (pintype "bidirectional"))
    )
    (net (code "55") (name "unconnected-(U2A-PA13(SWDIO)-Pad34)") (class "Default")
      (node (ref "U2") (pin "34") (pinfunction "PA13(SWDIO)_34") (pintype "bidirectional"))
    )
    (net (code "56") (name "unconnected-(U2A-PB0-Pad18)") (class "Default")
      (node (ref "U2") (pin "18") (pinfunction "PB0_18") (pintype "bidirectional"))
    )
    (net (code "57") (name "unconnected-(U2A-PB8-Pad45)") (class "Default")
      (node (ref "U2") (pin "45") (pinfunction "PB8_45") (pintype "bidirectional"))
    )
    (net (code "58") (name "unconnected-(U2A-PB9-Pad46)") (class "Default")
      (node (ref "U2") (pin "46") (pinfunction "PB9_46") (pintype "bidirectional"))
    )
    (net (code "59") (name "unconnected-(U2A-PB10-Pad21)") (class "Default")
      (node (ref "U2") (pin "21") (pinfunction "PB10_21") (pintype "bidirectional"))
    )
    (net (code "60") (name "unconnected-(U2A-PB11-Pad22)") (class "Default")
      (node (ref "U2") (pin "22") (pinfunction "PB11_22") (pintype "bidirectional"))
    )
    (net (code "61") (name "unconnected-(U2A-PC13-Pad2)") (class "Default")
      (node (ref "U2") (pin "2") (pinfunction "PC13_2") (pintype "bidirectional"))
    )
    (net (code "62") (name "unconnected-(U2A-PC14-OSC32_IN(PC14)-Pad3)") (class "Default")
      (node (ref "U2") (pin "3") (pinfunction "PC14-OSC32_IN(PC14)_3") (pintype "bidirectional"))
    )
    (net (code "63") (name "unconnected-(U2A-PC15-OSC32_OUT(PC15)-Pad4)") (class "Default")
      (node (ref "U2") (pin "4") (pinfunction "PC15-OSC32_OUT(PC15)_4") (pintype "bidirectional"))
    )
    (net (code "64") (name "unconnected-(U3B-V+-Pad8)") (class "Default")
      (node (ref "U3") (pin "8") (pinfunction "V+_8") (pintype "power_in"))
    )
    (net (code "65") (name "unconnected-(U3B-V--Pad4)") (class "Default")
      (node (ref "U3") (pin "4") (pinfunction "V-_4") (pintype "power_in"))
    )
    (net (code "66") (name "unconnected-(U7B-V+-Pad8)") (class "Default")
      (node (ref "U7") (pin "8") (pinfunction "V+_8") (pintype "power_in"))
    )
    (net (code "67") (name "unconnected-(U7B-V--Pad4)") (class "Default")
      (node (ref "U7") (pin "4") (pinfunction "V-_4") (pintype "power_in"))
    )
  )
)
